# board.net
KiCad netlist of a schematic drawn in EAGLE
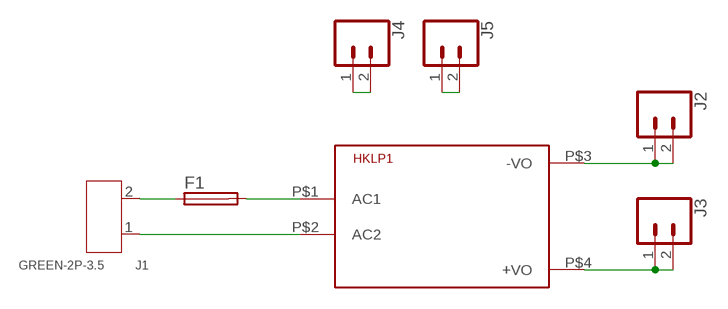
[diagram p0: schematic, sheet 1]

(export (version "E")
  (design (tool "Eeschema 10.0.6"))
  (components
    (comp (ref "F1")
      (value "TR5")
      (footprint "eagle-import:TR5")
      (libsource (lib "eagle-import") (part "TR5"))
    )
    (comp (ref "HKLP1")
      (value "HKLPM01")
      (footprint "eagle-import:HKLPM01")
      (libsource (lib "eagle-import") (part "HKLPM01"))
    )
    (comp (ref "J1")
      (value "GREEN-2P-3.5")
      (footprint "eagle-import:H2-3.5-7.0X7.0MM")
      (libsource (lib "eagle-import") (part "SCREW-TERMINAL-GREEN(2P-3.5)"))
    )
    (comp (ref "J2")
      (value "CONN_02")
      (footprint "eagle-import:1X02")
      (libsource (lib "eagle-import") (part "CONN_02"))
    )
    (comp (ref "J3")
      (value "CONN_02")
      (footprint "eagle-import:1X02")
      (libsource (lib "eagle-import") (part "CONN_02"))
    )
    (comp (ref "J4")
      (value "CONN_02")
      (footprint "eagle-import:1X02")
      (libsource (lib "eagle-import") (part "CONN_02"))
    )
    (comp (ref "J5")
      (value "CONN_02")
      (footprint "eagle-import:1X02")
      (libsource (lib "eagle-import") (part "CONN_02"))
    )
  )
  (nets
    (net (code "1") (name "Net-(F1-Pad1)") (class "Default")
      (node (ref "F1") (pin "1") (pinfunction "1_1") (pintype "passive"))
      (node (ref "J1") (pin "2") (pinfunction "2_2") (pintype "bidirectional"))
    )
    (net (code "2") (name "Net-(HKLP1-+VO)") (class "Default")
      (node (ref "HKLP1") (pin "P$4") (pinfunction "+VO_P$4") (pintype "bidirectional"))
      (node (ref "J3") (pin "1") (pinfunction "1_1") (pintype "passive"))
      (node (ref "J3") (pin "2") (pinfunction "2_2") (pintype "passive"))
    )
    (net (code "3") (name "Net-(HKLP1--VO)") (class "Default")
      (node (ref "HKLP1") (pin "P$3") (pinfunction "-VO_P$3") (pintype "bidirectional"))
      (node (ref "J2") (pin "1") (pinfunction "1_1") (pintype "passive"))
      (node (ref "J2") (pin "2") (pinfunction "2_2") (pintype "passive"))
    )
    (net (code "4") (name "Net-(HKLP1-AC1)") (class "Default")
      (node (ref "F1") (pin "2") (pinfunction "2_2") (pintype "passive"))
      (node (ref "HKLP1") (pin "P$1") (pinfunction "AC1_P$1") (pintype "bidirectional"))
    )
    (net (code "5") (name "Net-(HKLP1-AC2)") (class "Default")
      (node (ref "HKLP1") (pin "P$2") (pinfunction "AC2_P$2") (pintype "bidirectional"))
      (node (ref "J1") (pin "1") (pinfunction "1_1") (pintype "bidirectional"))
    )
    (net (code "6") (name "Net-(J4-Pad1)") (class "Default")
      (node (ref "J4") (pin "1") (pinfunction "1_1") (pintype "passive"))
      (node (ref "J4") (pin "2") (pinfunction "2_2") (pintype "passive"))
    )
    (net (code "7") (name "Net-(J5-Pad1)") (class "Default")
      (node (ref "J5") (pin "1") (pinfunction "1_1") (pintype "passive"))
      (node (ref "J5") (pin "2") (pinfunction "2_2") (pintype "passive"))
    )
  )
)
